# M113D.net
KiCad netlist of a schematic drawn in EAGLE
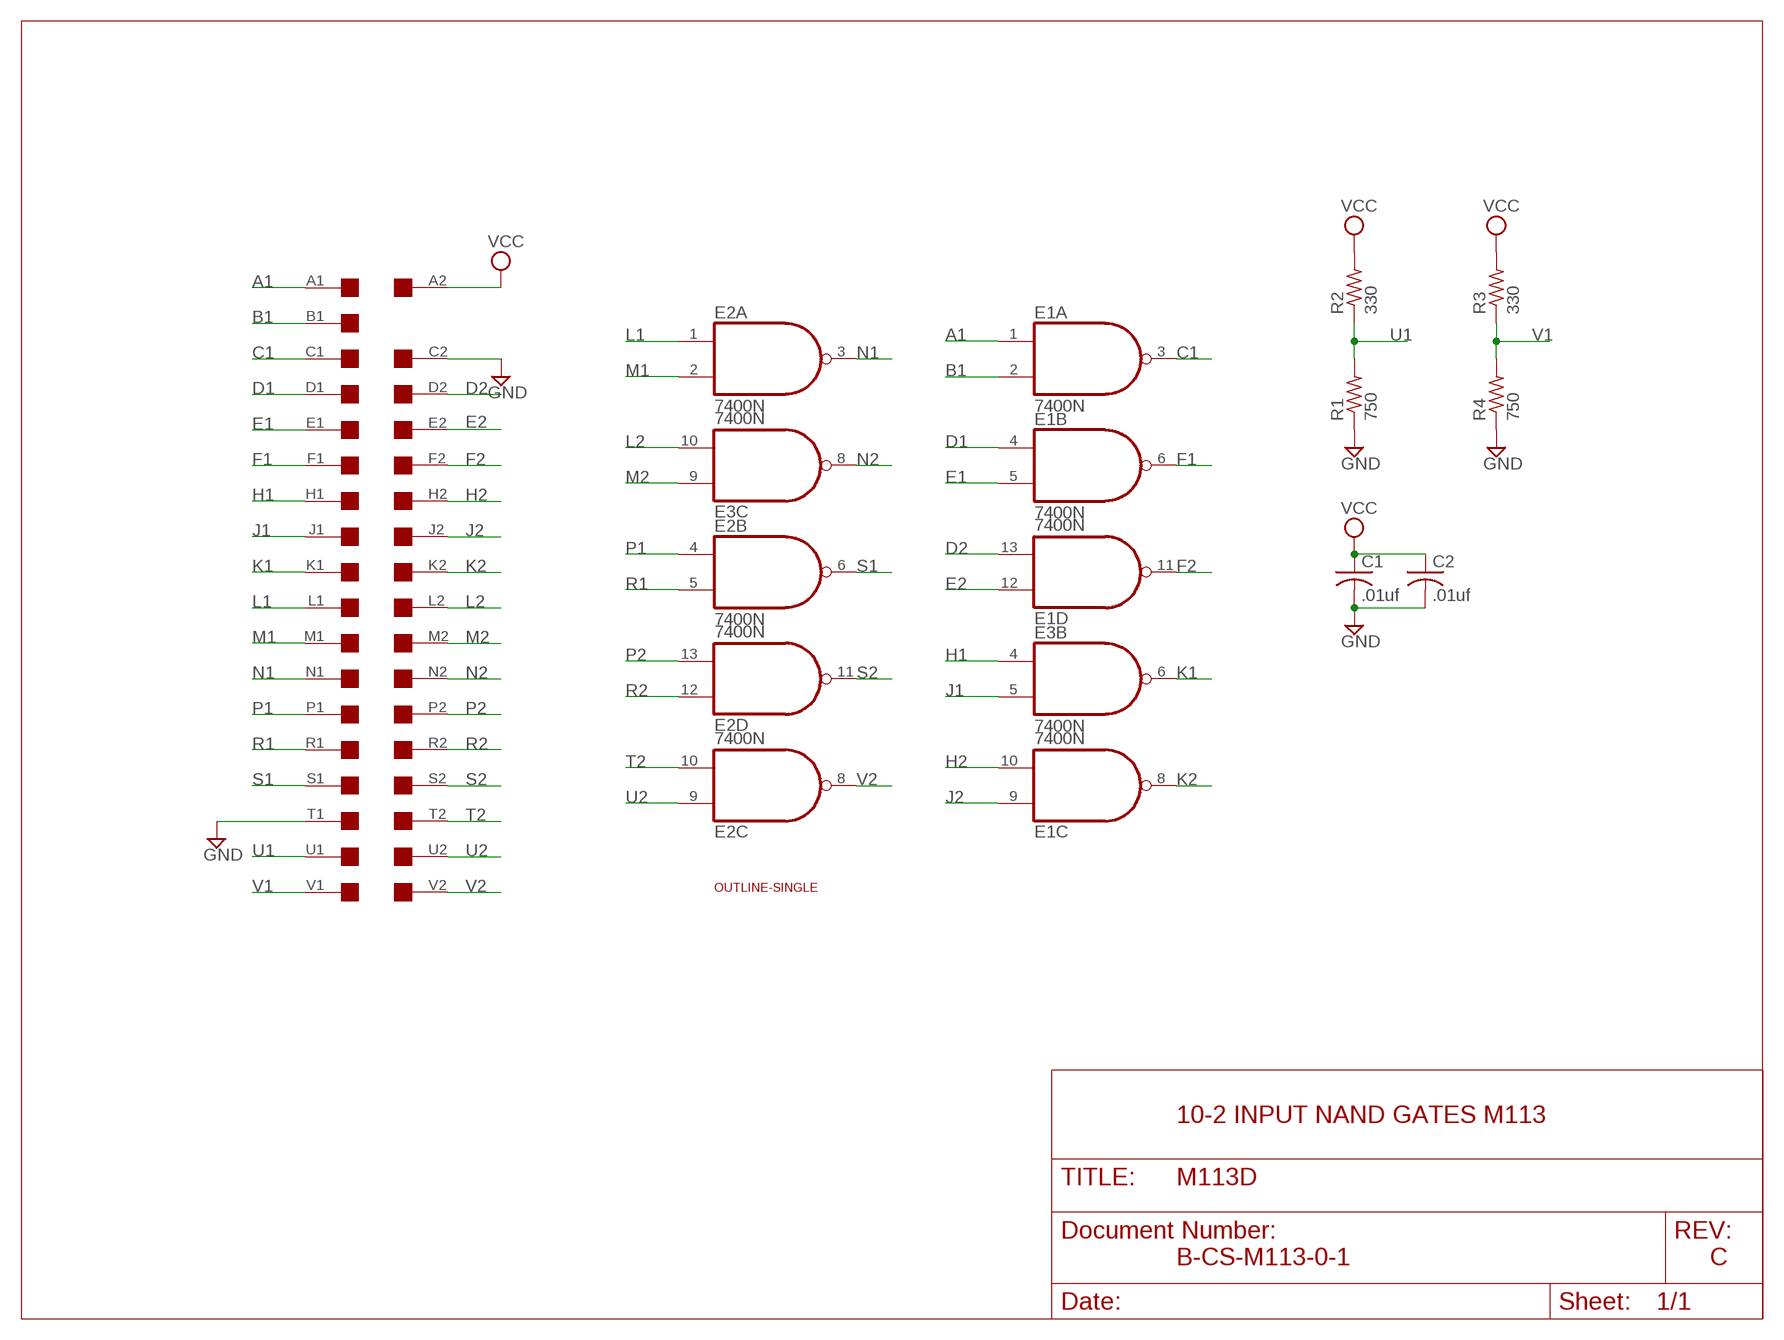
[diagram p0: schematic, sheet 1]

(export (version "E")
  (design (tool "Eeschema 10.0.6"))
  (components
    (comp (ref "C1")
      (value ".01uf")
      (footprint "eagle-import:C050-025X075")
      (libsource (lib "eagle-import") (part "C-US050-025X075"))
    )
    (comp (ref "C2")
      (value ".01uf")
      (footprint "eagle-import:C050-025X075")
      (libsource (lib "eagle-import") (part "C-US050-025X075"))
    )
    (comp (ref "E1")
      (value "7400N")
      (footprint "eagle-import:DIL14")
      (libsource (lib "eagle-import") (part "7400N"))
    )
    (comp (ref "E2")
      (value "7400N")
      (footprint "eagle-import:DIL14")
      (libsource (lib "eagle-import") (part "7400N"))
    )
    (comp (ref "E3")
      (value "7400N")
      (footprint "eagle-import:DIL14")
      (libsource (lib "eagle-import") (part "7400N"))
    )
    (comp (ref "R1")
      (value "750")
      (footprint "eagle-import:0207_10")
      (libsource (lib "eagle-import") (part "R-US_0207/10"))
    )
    (comp (ref "R2")
      (value "330")
      (footprint "eagle-import:0207_10")
      (libsource (lib "eagle-import") (part "R-US_0207/10"))
    )
    (comp (ref "R3")
      (value "330")
      (footprint "eagle-import:0207_10")
      (libsource (lib "eagle-import") (part "R-US_0207/10"))
    )
    (comp (ref "R4")
      (value "750")
      (footprint "eagle-import:0207_10")
      (libsource (lib "eagle-import") (part "R-US_0207/10"))
    )
    (comp (ref "U$1")
      (value "SINGLE")
      (footprint "eagle-import:EDGE-CON2")
      (libsource (lib "eagle-import") (part "SINGLE"))
    )
    (comp (ref "U$2")
      (value "OUTLINE-SINGLE")
      (footprint "eagle-import:SINGLE")
      (libsource (lib "eagle-import") (part "OUTLINE-SINGLE"))
    )
  )
  (nets
    (net (code "1") (name "/A1") (class "Default")
      (node (ref "E1") (pin "1") (pinfunction "I0_1") (pintype "input"))
      (node (ref "U$1") (pin "A1") (pinfunction "1_A1") (pintype "bidirectional"))
    )
    (net (code "2") (name "/B1") (class "Default")
      (node (ref "E1") (pin "2") (pinfunction "I1_2") (pintype "input"))
      (node (ref "U$1") (pin "B1") (pinfunction "1_B1") (pintype "bidirectional"))
    )
    (net (code "3") (name "/C1") (class "Default")
      (node (ref "E1") (pin "3") (pinfunction "O_3") (pintype "output"))
      (node (ref "U$1") (pin "C1") (pinfunction "1_C1") (pintype "bidirectional"))
    )
    (net (code "4") (name "/D1") (class "Default")
      (node (ref "E1") (pin "4") (pinfunction "I0_4") (pintype "input"))
      (node (ref "U$1") (pin "D1") (pinfunction "1_D1") (pintype "bidirectional"))
    )
    (net (code "5") (name "/D2") (class "Default")
      (node (ref "E1") (pin "13") (pinfunction "I1_13") (pintype "input"))
      (node (ref "U$1") (pin "D2") (pinfunction "1_D2") (pintype "bidirectional"))
    )
    (net (code "6") (name "/E1") (class "Default")
      (node (ref "E1") (pin "5") (pinfunction "I1_5") (pintype "input"))
      (node (ref "U$1") (pin "E1") (pinfunction "1_E1") (pintype "bidirectional"))
    )
    (net (code "7") (name "/E2") (class "Default")
      (node (ref "E1") (pin "12") (pinfunction "I0_12") (pintype "input"))
      (node (ref "U$1") (pin "E2") (pinfunction "1_E2") (pintype "bidirectional"))
    )
    (net (code "8") (name "/F1") (class "Default")
      (node (ref "E1") (pin "6") (pinfunction "O_6") (pintype "output"))
      (node (ref "U$1") (pin "F1") (pinfunction "1_F1") (pintype "bidirectional"))
    )
    (net (code "9") (name "/F2") (class "Default")
      (node (ref "E1") (pin "11") (pinfunction "O_11") (pintype "output"))
      (node (ref "U$1") (pin "F2") (pinfunction "1_F2") (pintype "bidirectional"))
    )
    (net (code "10") (name "/H1") (class "Default")
      (node (ref "E3") (pin "4") (pinfunction "I0_4") (pintype "input"))
      (node (ref "U$1") (pin "H1") (pinfunction "1_H1") (pintype "bidirectional"))
    )
    (net (code "11") (name "/H2") (class "Default")
      (node (ref "E1") (pin "10") (pinfunction "I1_10") (pintype "input"))
      (node (ref "U$1") (pin "H2") (pinfunction "1_H2") (pintype "bidirectional"))
    )
    (net (code "12") (name "/J1") (class "Default")
      (node (ref "E3") (pin "5") (pinfunction "I1_5") (pintype "input"))
      (node (ref "U$1") (pin "J1") (pinfunction "1_J1") (pintype "bidirectional"))
    )
    (net (code "13") (name "/J2") (class "Default")
      (node (ref "E1") (pin "9") (pinfunction "I0_9") (pintype "input"))
      (node (ref "U$1") (pin "J2") (pinfunction "1_J2") (pintype "bidirectional"))
    )
    (net (code "14") (name "/K1") (class "Default")
      (node (ref "E3") (pin "6") (pinfunction "O_6") (pintype "output"))
      (node (ref "U$1") (pin "K1") (pinfunction "1_K1") (pintype "bidirectional"))
    )
    (net (code "15") (name "/K2") (class "Default")
      (node (ref "E1") (pin "8") (pinfunction "O_8") (pintype "output"))
      (node (ref "U$1") (pin "K2") (pinfunction "1_K2") (pintype "bidirectional"))
    )
    (net (code "16") (name "/L1") (class "Default")
      (node (ref "E2") (pin "1") (pinfunction "I0_1") (pintype "input"))
      (node (ref "U$1") (pin "L1") (pinfunction "1_L1") (pintype "bidirectional"))
    )
    (net (code "17") (name "/L2") (class "Default")
      (node (ref "E3") (pin "10") (pinfunction "I1_10") (pintype "input"))
      (node (ref "U$1") (pin "L2") (pinfunction "1_L2") (pintype "bidirectional"))
    )
    (net (code "18") (name "/M1") (class "Default")
      (node (ref "E2") (pin "2") (pinfunction "I1_2") (pintype "input"))
      (node (ref "U$1") (pin "M1") (pinfunction "1_M1") (pintype "bidirectional"))
    )
    (net (code "19") (name "/M2") (class "Default")
      (node (ref "E3") (pin "9") (pinfunction "I0_9") (pintype "input"))
      (node (ref "U$1") (pin "M2") (pinfunction "1_M2") (pintype "bidirectional"))
    )
    (net (code "20") (name "/N1") (class "Default")
      (node (ref "E2") (pin "3") (pinfunction "O_3") (pintype "output"))
      (node (ref "U$1") (pin "N1") (pinfunction "1_N1") (pintype "bidirectional"))
    )
    (net (code "21") (name "/N2") (class "Default")
      (node (ref "E3") (pin "8") (pinfunction "O_8") (pintype "output"))
      (node (ref "U$1") (pin "N2") (pinfunction "1_N2") (pintype "bidirectional"))
    )
    (net (code "22") (name "/P1") (class "Default")
      (node (ref "E2") (pin "4") (pinfunction "I0_4") (pintype "input"))
      (node (ref "U$1") (pin "P1") (pinfunction "1_P1") (pintype "bidirectional"))
    )
    (net (code "23") (name "/P2") (class "Default")
      (node (ref "E2") (pin "13") (pinfunction "I1_13") (pintype "input"))
      (node (ref "U$1") (pin "P2") (pinfunction "1_P2") (pintype "bidirectional"))
    )
    (net (code "24") (name "/R1") (class "Default")
      (node (ref "E2") (pin "5") (pinfunction "I1_5") (pintype "input"))
      (node (ref "U$1") (pin "R1") (pinfunction "1_R1") (pintype "bidirectional"))
    )
    (net (code "25") (name "/R2") (class "Default")
      (node (ref "E2") (pin "12") (pinfunction "I0_12") (pintype "input"))
      (node (ref "U$1") (pin "R2") (pinfunction "1_R2") (pintype "bidirectional"))
    )
    (net (code "26") (name "/S1") (class "Default")
      (node (ref "E2") (pin "6") (pinfunction "O_6") (pintype "output"))
      (node (ref "U$1") (pin "S1") (pinfunction "1_S1") (pintype "bidirectional"))
    )
    (net (code "27") (name "/S2") (class "Default")
      (node (ref "E2") (pin "11") (pinfunction "O_11") (pintype "output"))
      (node (ref "U$1") (pin "S2") (pinfunction "1_S2") (pintype "bidirectional"))
    )
    (net (code "28") (name "/T2") (class "Default")
      (node (ref "E2") (pin "10") (pinfunction "I1_10") (pintype "input"))
      (node (ref "U$1") (pin "T2") (pinfunction "1_T2") (pintype "bidirectional"))
    )
    (net (code "29") (name "/U1") (class "Default")
      (node (ref "R1") (pin "2") (pinfunction "2_2") (pintype "passive"))
      (node (ref "R2") (pin "1") (pinfunction "1_1") (pintype "passive"))
      (node (ref "U$1") (pin "U1") (pinfunction "1_U1") (pintype "bidirectional"))
    )
    (net (code "30") (name "/U2") (class "Default")
      (node (ref "E2") (pin "9") (pinfunction "I0_9") (pintype "input"))
      (node (ref "U$1") (pin "U2") (pinfunction "1_U2") (pintype "bidirectional"))
    )
    (net (code "31") (name "/V1") (class "Default")
      (node (ref "R3") (pin "1") (pinfunction "1_1") (pintype "passive"))
      (node (ref "R4") (pin "2") (pinfunction "2_2") (pintype "passive"))
      (node (ref "U$1") (pin "V1") (pinfunction "1_V1") (pintype "bidirectional"))
    )
    (net (code "32") (name "/V2") (class "Default")
      (node (ref "E2") (pin "8") (pinfunction "O_8") (pintype "output"))
      (node (ref "U$1") (pin "V2") (pinfunction "1_V2") (pintype "bidirectional"))
    )
    (net (code "33") (name "GND") (class "Default")
      (node (ref "C1") (pin "2") (pinfunction "2_2") (pintype "passive"))
      (node (ref "C2") (pin "2") (pinfunction "2_2") (pintype "passive"))
      (node (ref "R1") (pin "1") (pinfunction "1_1") (pintype "passive"))
      (node (ref "R4") (pin "1") (pinfunction "1_1") (pintype "passive"))
      (node (ref "U$1") (pin "C2") (pinfunction "1_C2") (pintype "bidirectional"))
      (node (ref "U$1") (pin "T1") (pinfunction "1_T1") (pintype "bidirectional"))
    )
    (net (code "34") (name "VCC") (class "Default")
      (node (ref "C1") (pin "1") (pinfunction "1_1") (pintype "passive"))
      (node (ref "C2") (pin "1") (pinfunction "1_1") (pintype "passive"))
      (node (ref "R2") (pin "2") (pinfunction "2_2") (pintype "passive"))
      (node (ref "R3") (pin "2") (pinfunction "2_2") (pintype "passive"))
      (node (ref "U$1") (pin "A2") (pinfunction "1_A2") (pintype "bidirectional"))
    )
  )
)
